# RFM2Pi_v2_5.net
KiCad netlist of a schematic drawn in EAGLE
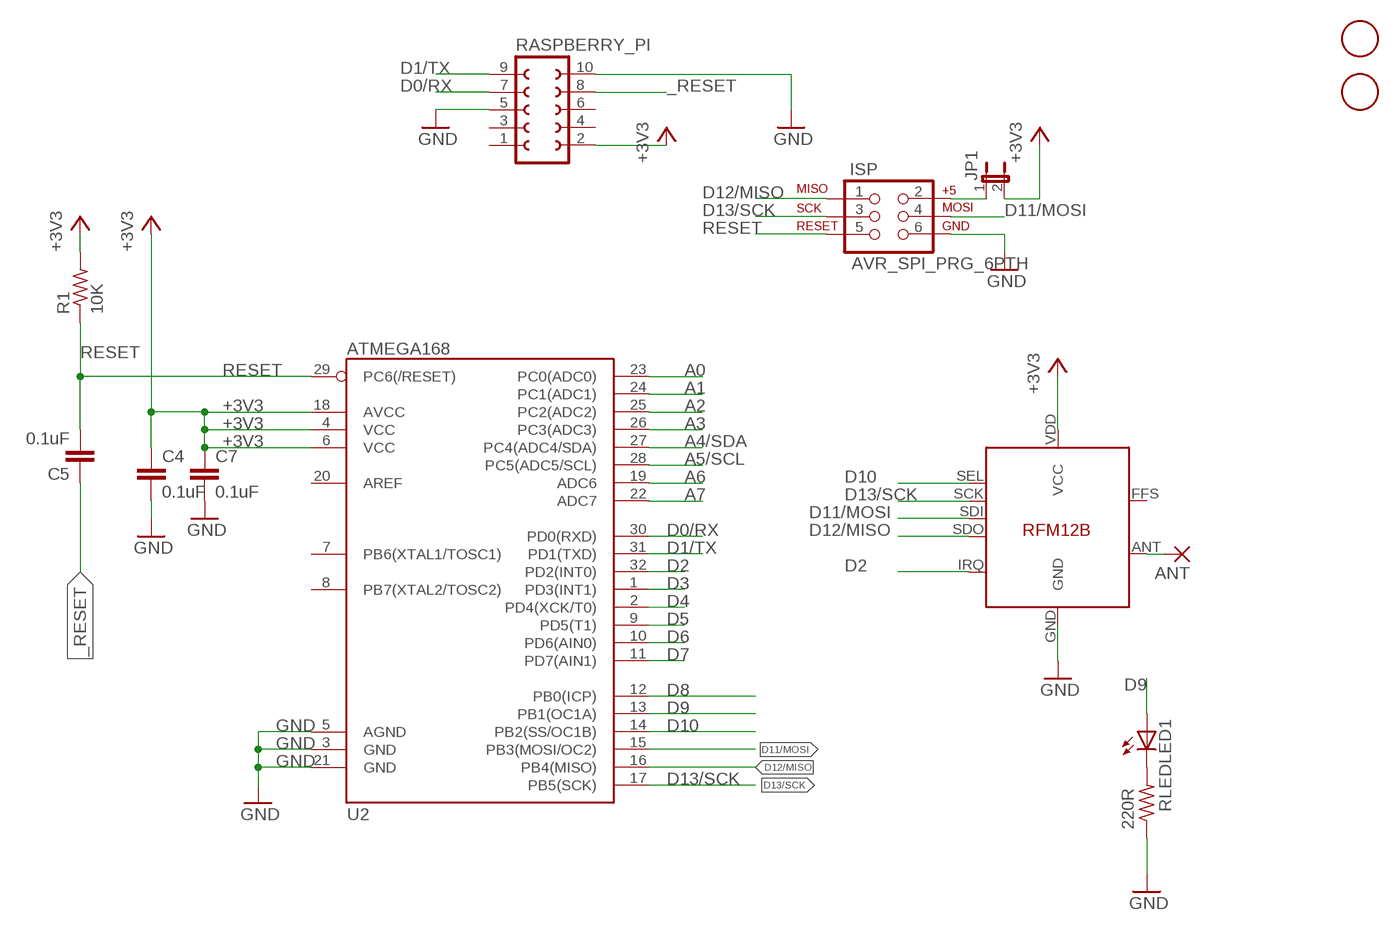
[diagram p0: schematic, sheet 1]

(export (version "E")
  (design (tool "Eeschema 10.0.6"))
  (components
    (comp (ref "ANT")
      (value "1,6/0,8")
      (footprint "eagle-import:1,6_0,8")
      (libsource (lib "eagle-import") (part "1,6/0,8"))
    )
    (comp (ref "C4")
      (value "0.1uF")
      (footprint "eagle-import:C0603")
      (libsource (lib "eagle-import") (part "C-EUC0603"))
    )
    (comp (ref "C5")
      (value "0.1uF")
      (footprint "eagle-import:C0603")
      (libsource (lib "eagle-import") (part "C-EUC0603"))
    )
    (comp (ref "C7")
      (value "0.1uF")
      (footprint "eagle-import:C0603")
      (libsource (lib "eagle-import") (part "resistor_C-EUC0603"))
    )
    (comp (ref "ISP")
      (value "AVR_SPI_PRG_6PTH")
      (footprint "eagle-import:2X3")
      (libsource (lib "eagle-import") (part "AVR_SPI_PRG_6PTH"))
    )
    (comp (ref "JP1")
      (value "JUMPER-2PTH")
      (footprint "eagle-import:1X02")
      (libsource (lib "eagle-import") (part "JUMPER-2PTH"))
    )
    (comp (ref "LED1")
      (value "LEDSML0603")
      (footprint "eagle-import:SML0603")
      (libsource (lib "eagle-import") (part "LEDSML0603"))
    )
    (comp (ref "R1")
      (value "10K")
      (footprint "eagle-import:R0603")
      (libsource (lib "eagle-import") (part "R-US_R0603"))
    )
    (comp (ref "RASPBERRY_PI")
      (value "FE05-2")
      (footprint "eagle-import:FE05-2")
      (libsource (lib "eagle-import") (part "FE05-2"))
    )
    (comp (ref "RFM12B")
      (value "RFM12B")
      (footprint "eagle-import:RFM12B")
      (libsource (lib "eagle-import") (part "RFM12B"))
    )
    (comp (ref "RLED")
      (value "220R")
      (footprint "eagle-import:R0603")
      (libsource (lib "eagle-import") (part "R-US_R0603"))
    )
    (comp (ref "U$1")
      (value "FIDUCIAL")
      (footprint "eagle-import:FIDUCIAL_1MM")
      (libsource (lib "eagle-import") (part "FIDUCIAL"))
    )
    (comp (ref "U$2")
      (value "FIDUCIAL")
      (footprint "eagle-import:FIDUCIAL_1MM")
      (libsource (lib "eagle-import") (part "FIDUCIAL"))
    )
    (comp (ref "U2")
      (value "ATMEGA168")
      (footprint "eagle-import:TQFP32-08")
      (libsource (lib "eagle-import") (part "ATMEGA168"))
    )
  )
  (nets
    (net (code "1") (name "+3V3") (class "Default")
      (node (ref "C4") (pin "1") (pinfunction "1_1") (pintype "passive"))
      (node (ref "C7") (pin "1") (pinfunction "1_1") (pintype "passive"))
      (node (ref "JP1") (pin "2") (pinfunction "2_2") (pintype "passive"))
      (node (ref "R1") (pin "2") (pinfunction "2_2") (pintype "passive"))
      (node (ref "RASPBERRY_PI") (pin "2") (pinfunction "2_2") (pintype "passive"))
      (node (ref "RFM12B") (pin "VDD") (pinfunction "VCC_VDD") (pintype "power_in"))
      (node (ref "U2") (pin "18") (pinfunction "AVCC_18") (pintype "bidirectional"))
      (node (ref "U2") (pin "4") (pinfunction "VCC_4") (pintype "bidirectional"))
      (node (ref "U2") (pin "6") (pinfunction "VCC_6") (pintype "bidirectional"))
    )
    (net (code "2") (name "/A0") (class "Default")
      (node (ref "U2") (pin "23") (pinfunction "PC0(ADC0)_23") (pintype "bidirectional"))
    )
    (net (code "3") (name "/A1") (class "Default")
      (node (ref "U2") (pin "24") (pinfunction "PC1(ADC1)_24") (pintype "bidirectional"))
    )
    (net (code "4") (name "/A2") (class "Default")
      (node (ref "U2") (pin "25") (pinfunction "PC2(ADC2)_25") (pintype "bidirectional"))
    )
    (net (code "5") (name "/A3") (class "Default")
      (node (ref "U2") (pin "26") (pinfunction "PC3(ADC3)_26") (pintype "bidirectional"))
    )
    (net (code "6") (name "/A4{slash}SDA") (class "Default")
      (node (ref "U2") (pin "27") (pinfunction "PC4(ADC4/SDA)_27") (pintype "bidirectional"))
    )
    (net (code "7") (name "/A5{slash}SCL") (class "Default")
      (node (ref "U2") (pin "28") (pinfunction "PC5(ADC5/SCL)_28") (pintype "bidirectional"))
    )
    (net (code "8") (name "/A6") (class "Default")
      (node (ref "U2") (pin "19") (pinfunction "ADC6_19") (pintype "bidirectional"))
    )
    (net (code "9") (name "/A7") (class "Default")
      (node (ref "U2") (pin "22") (pinfunction "ADC7_22") (pintype "bidirectional"))
    )
    (net (code "10") (name "/D0{slash}RX") (class "Default")
      (node (ref "RASPBERRY_PI") (pin "7") (pinfunction "7_7") (pintype "passive"))
      (node (ref "U2") (pin "30") (pinfunction "PD0(RXD)_30") (pintype "bidirectional"))
    )
    (net (code "11") (name "/D1{slash}TX") (class "Default")
      (node (ref "RASPBERRY_PI") (pin "9") (pinfunction "9_9") (pintype "passive"))
      (node (ref "U2") (pin "31") (pinfunction "PD1(TXD)_31") (pintype "bidirectional"))
    )
    (net (code "12") (name "/D2") (class "Default")
      (node (ref "RFM12B") (pin "IRQ") (pinfunction "IRQ_IRQ") (pintype "open_collector"))
      (node (ref "U2") (pin "32") (pinfunction "PD2(INT0)_32") (pintype "bidirectional"))
    )
    (net (code "13") (name "/D3") (class "Default")
      (node (ref "U2") (pin "1") (pinfunction "PD3(INT1)_1") (pintype "bidirectional"))
    )
    (net (code "14") (name "/D4") (class "Default")
      (node (ref "U2") (pin "2") (pinfunction "PD4(XCK/T0)_2") (pintype "bidirectional"))
    )
    (net (code "15") (name "/D5") (class "Default")
      (node (ref "U2") (pin "9") (pinfunction "PD5(T1)_9") (pintype "bidirectional"))
    )
    (net (code "16") (name "/D6") (class "Default")
      (node (ref "U2") (pin "10") (pinfunction "PD6(AIN0)_10") (pintype "bidirectional"))
    )
    (net (code "17") (name "/D7") (class "Default")
      (node (ref "U2") (pin "11") (pinfunction "PD7(AIN1)_11") (pintype "bidirectional"))
    )
    (net (code "18") (name "/D8") (class "Default")
      (node (ref "U2") (pin "12") (pinfunction "PB0(ICP)_12") (pintype "bidirectional"))
    )
    (net (code "19") (name "/D9") (class "Default")
      (node (ref "LED1") (pin "A") (pinfunction "A_A") (pintype "passive"))
      (node (ref "U2") (pin "13") (pinfunction "PB1(OC1A)_13") (pintype "bidirectional"))
    )
    (net (code "20") (name "/D10") (class "Default")
      (node (ref "RFM12B") (pin "SEL") (pinfunction "SEL_SEL") (pintype "input"))
      (node (ref "U2") (pin "14") (pinfunction "PB2(SS/OC1B)_14") (pintype "bidirectional"))
    )
    (net (code "21") (name "/RESET") (class "Default")
      (node (ref "C5") (pin "2") (pinfunction "2_2") (pintype "passive"))
      (node (ref "ISP") (pin "5") (pinfunction "5_5") (pintype "passive"))
      (node (ref "R1") (pin "1") (pinfunction "1_1") (pintype "passive"))
      (node (ref "U2") (pin "29") (pinfunction "PC6(/RESET)_29") (pintype "bidirectional"))
    )
    (net (code "22") (name "D11{slash}MOSI") (class "Default")
      (node (ref "ISP") (pin "4") (pinfunction "4_4") (pintype "passive"))
      (node (ref "RFM12B") (pin "SDI") (pinfunction "SDI_SDI") (pintype "input"))
      (node (ref "U2") (pin "15") (pinfunction "PB3(MOSI/OC2)_15") (pintype "bidirectional"))
    )
    (net (code "23") (name "D12{slash}MISO") (class "Default")
      (node (ref "ISP") (pin "1") (pinfunction "1_1") (pintype "passive"))
      (node (ref "RFM12B") (pin "SDO") (pinfunction "SDO_SDO") (pintype "output"))
      (node (ref "U2") (pin "16") (pinfunction "PB4(MISO)_16") (pintype "bidirectional"))
    )
    (net (code "24") (name "D13{slash}SCK") (class "Default")
      (node (ref "ISP") (pin "3") (pinfunction "3_3") (pintype "passive"))
      (node (ref "RFM12B") (pin "SCK") (pinfunction "SCK_SCK") (pintype "input"))
      (node (ref "U2") (pin "17") (pinfunction "PB5(SCK)_17") (pintype "bidirectional"))
    )
    (net (code "25") (name "GND") (class "Default")
      (node (ref "C4") (pin "2") (pinfunction "2_2") (pintype "passive"))
      (node (ref "C7") (pin "2") (pinfunction "2_2") (pintype "passive"))
      (node (ref "ISP") (pin "6") (pinfunction "6_6") (pintype "passive"))
      (node (ref "RASPBERRY_PI") (pin "10") (pinfunction "10_10") (pintype "passive"))
      (node (ref "RASPBERRY_PI") (pin "5") (pinfunction "5_5") (pintype "passive"))
      (node (ref "RFM12B") (pin "GND") (pinfunction "GND_GND") (pintype "power_in"))
      (node (ref "RLED") (pin "1") (pinfunction "1_1") (pintype "passive"))
      (node (ref "U2") (pin "21") (pinfunction "GND_21") (pintype "bidirectional"))
      (node (ref "U2") (pin "3") (pinfunction "GND_3") (pintype "bidirectional"))
      (node (ref "U2") (pin "5") (pinfunction "AGND_5") (pintype "bidirectional"))
    )
    (net (code "26") (name "Net-(ANT-P)") (class "Default")
      (node (ref "ANT") (pin "1") (pinfunction "P_1") (pintype "passive"))
      (node (ref "RFM12B") (pin "ANT") (pinfunction "ANT_ANT") (pintype "passive"))
    )
    (net (code "27") (name "Net-(ISP-Pad2)") (class "Default")
      (node (ref "ISP") (pin "2") (pinfunction "2_2") (pintype "passive"))
      (node (ref "JP1") (pin "1") (pinfunction "1_1") (pintype "passive"))
    )
    (net (code "28") (name "Net-(LED1-PadC)") (class "Default")
      (node (ref "LED1") (pin "C") (pinfunction "C_C") (pintype "passive"))
      (node (ref "RLED") (pin "2") (pinfunction "2_2") (pintype "passive"))
    )
    (net (code "29") (name "_RESET") (class "Default")
      (node (ref "C5") (pin "1") (pinfunction "1_1") (pintype "passive"))
      (node (ref "RASPBERRY_PI") (pin "8") (pinfunction "8_8") (pintype "passive"))
    )
    (net (code "30") (name "unconnected-(RASPBERRY_PI-Pad1)") (class "Default")
      (node (ref "RASPBERRY_PI") (pin "1") (pinfunction "1_1") (pintype "passive"))
    )
    (net (code "31") (name "unconnected-(RASPBERRY_PI-Pad3)") (class "Default")
      (node (ref "RASPBERRY_PI") (pin "3") (pinfunction "3_3") (pintype "passive"))
    )
    (net (code "32") (name "unconnected-(RASPBERRY_PI-Pad4)") (class "Default")
      (node (ref "RASPBERRY_PI") (pin "4") (pinfunction "4_4") (pintype "passive"))
    )
    (net (code "33") (name "unconnected-(RASPBERRY_PI-Pad6)") (class "Default")
      (node (ref "RASPBERRY_PI") (pin "6") (pinfunction "6_6") (pintype "passive"))
    )
    (net (code "34") (name "unconnected-(RFM12B-PadFFS)") (class "Default")
      (node (ref "RFM12B") (pin "FFS") (pinfunction "FFS_FFS") (pintype "bidirectional"))
    )
    (net (code "35") (name "unconnected-(U2-AREF-Pad20)") (class "Default")
      (node (ref "U2") (pin "20") (pinfunction "AREF_20") (pintype "bidirectional"))
    )
    (net (code "36") (name "unconnected-(U2-PB6(XTAL1{slash}TOSC1)-Pad7)") (class "Default")
      (node (ref "U2") (pin "7") (pinfunction "PB6(XTAL1/TOSC1)_7") (pintype "bidirectional"))
    )
    (net (code "37") (name "unconnected-(U2-PB7(XTAL2{slash}TOSC2)-Pad8)") (class "Default")
      (node (ref "U2") (pin "8") (pinfunction "PB7(XTAL2/TOSC2)_8") (pintype "bidirectional"))
    )
  )
)
